# PCB_Draft_4.net
KiCad netlist of a schematic drawn in EAGLE
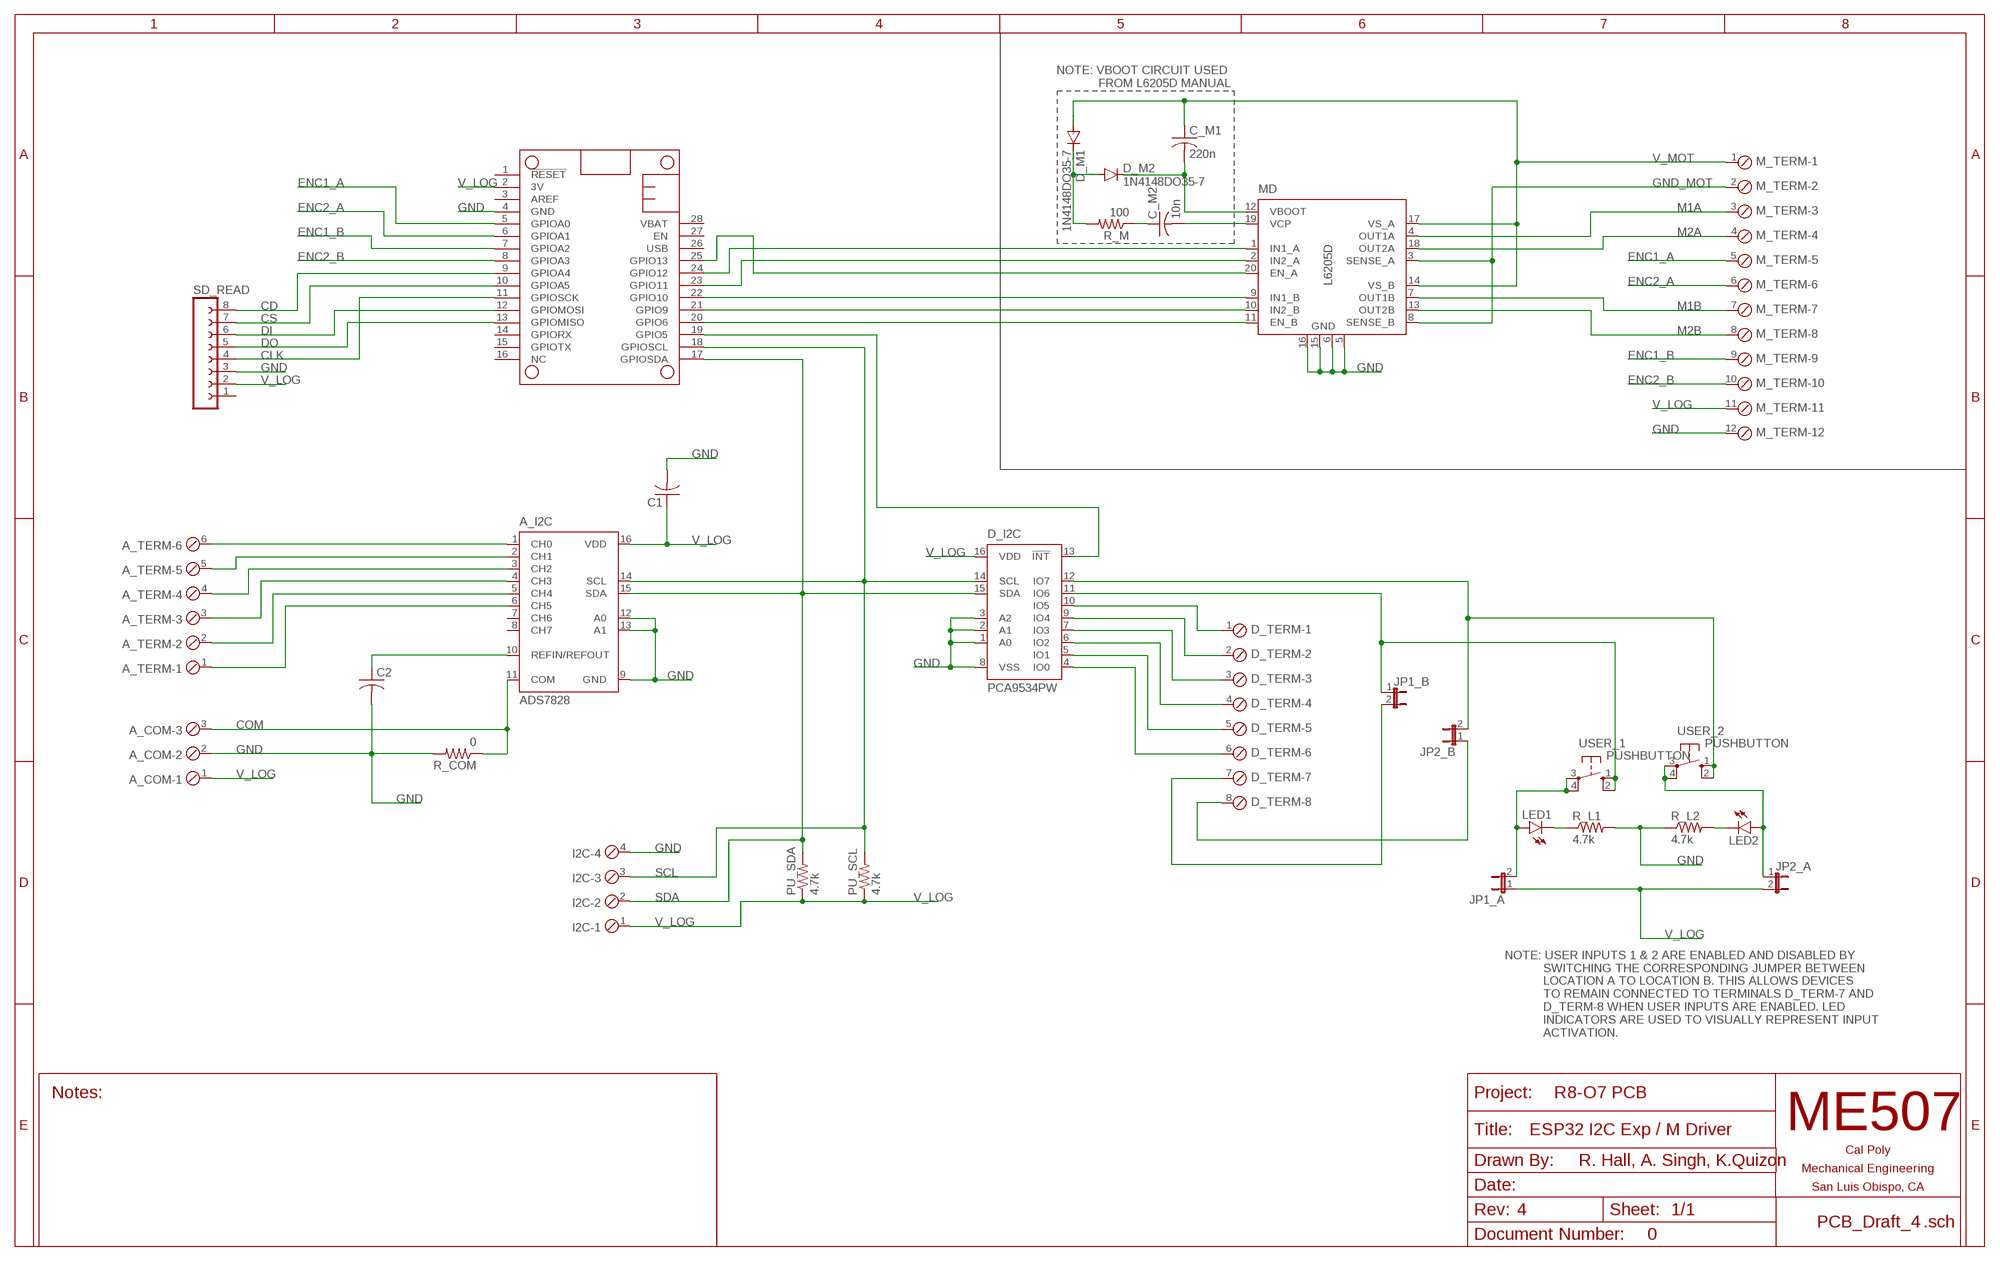
[diagram p0: schematic, sheet 1]

(export (version "E")
  (design (tool "Eeschema 10.0.6"))
  (components
    (comp (ref "A_COM")
      (value "SCREWTERM_3P_254")
      (footprint "eagle-import:3POL254")
      (libsource (lib "eagle-import") (part "SCREWTERM_3P_254"))
    )
    (comp (ref "A_I2C")
      (value "ADS7828")
      (footprint "eagle-import:TSSOP16-PW")
      (fields (field (name "MF") "TEXAS INSTRUMENTS") (field (name "MPN") "ADS7828E/250"))
      (libsource (lib "eagle-import") (part "ADS7828"))
    )
    (comp (ref "A_TERM")
      (value "SCREWTERM_6P_254")
      (footprint "eagle-import:6POL254")
      (libsource (lib "eagle-import") (part "SCREWTERM_6P_254"))
    )
    (comp (ref "C1")
      (value "C-USC0805")
      (footprint "eagle-import:C0805")
      (libsource (lib "eagle-import") (part "C-USC0805"))
    )
    (comp (ref "C2")
      (value "C-USC0805")
      (footprint "eagle-import:C0805")
      (libsource (lib "eagle-import") (part "C-USC0805"))
    )
    (comp (ref "C_M1")
      (value "220n")
      (footprint "eagle-import:C0805")
      (libsource (lib "eagle-import") (part "C-USC0805"))
    )
    (comp (ref "C_M2")
      (value "10n")
      (footprint "eagle-import:C0805")
      (libsource (lib "eagle-import") (part "C-USC0805"))
    )
    (comp (ref "D_I2C")
      (value "PCA9534PW")
      (footprint "eagle-import:TSSOP16")
      (libsource (lib "eagle-import") (part "PCA9534PW"))
    )
    (comp (ref "D_M1")
      (value "1N4148DO35-7")
      (footprint "eagle-import:DO35-7")
      (libsource (lib "eagle-import") (part "1N4148DO35-7"))
    )
    (comp (ref "D_M2")
      (value "1N4148DO35-7")
      (footprint "eagle-import:DO35-7")
      (libsource (lib "eagle-import") (part "1N4148DO35-7"))
    )
    (comp (ref "D_TERM")
      (value "SCREWTERM_8P_254")
      (footprint "eagle-import:8POL254")
      (libsource (lib "eagle-import") (part "SCREWTERM_8P_254"))
    )
    (comp (ref "FTHRWNG")
      (value "FEATHERWINGEXTENDED_BOTH_ENDS")
      (footprint "eagle-import:FEATHERWING")
      (libsource (lib "eagle-import") (part "FEATHERWINGEXTENDED_BOTH_ENDS"))
    )
    (comp (ref "I2C")
      (value "SCREWTERM_4P_254")
      (footprint "eagle-import:4POL254")
      (libsource (lib "eagle-import") (part "SCREWTERM_4P_254"))
    )
    (comp (ref "JP1_A")
      (value "JP1E")
      (footprint "eagle-import:JP1")
      (libsource (lib "eagle-import") (part "JP1E"))
    )
    (comp (ref "JP1_B")
      (value "JP1E")
      (footprint "eagle-import:JP1")
      (libsource (lib "eagle-import") (part "JP1E"))
    )
    (comp (ref "JP2_A")
      (value "JP1E")
      (footprint "eagle-import:JP1")
      (libsource (lib "eagle-import") (part "JP1E"))
    )
    (comp (ref "JP2_B")
      (value "JP1E")
      (footprint "eagle-import:JP1")
      (libsource (lib "eagle-import") (part "JP1E"))
    )
    (comp (ref "LED1")
      (value "LEDCHIP-LED0805")
      (footprint "eagle-import:CHIP-LED0805")
      (libsource (lib "eagle-import") (part "LEDCHIP-LED0805"))
    )
    (comp (ref "LED2")
      (value "LEDCHIP-LED0805")
      (footprint "eagle-import:CHIP-LED0805")
      (libsource (lib "eagle-import") (part "LEDCHIP-LED0805"))
    )
    (comp (ref "MD")
      (value "L6205D")
      (footprint "eagle-import:SO20")
      (libsource (lib "eagle-import") (part "L6205D"))
    )
    (comp (ref "M_TERM")
      (value "SCREWTERM_12P_254")
      (footprint "eagle-import:12POL254")
      (libsource (lib "eagle-import") (part "SCREWTERM_12P_254"))
    )
    (comp (ref "PU_SCL")
      (value "4.7k")
      (footprint "eagle-import:M0805")
      (libsource (lib "eagle-import") (part "R-US_M0805"))
    )
    (comp (ref "PU_SDA")
      (value "4.7k")
      (footprint "eagle-import:M0805")
      (libsource (lib "eagle-import") (part "R-US_M0805"))
    )
    (comp (ref "R_COM")
      (value "0")
      (footprint "eagle-import:M0805")
      (libsource (lib "eagle-import") (part "R-US_M0805"))
    )
    (comp (ref "R_L1")
      (value "4.7k")
      (footprint "eagle-import:M0805")
      (libsource (lib "eagle-import") (part "R-US_M0805"))
    )
    (comp (ref "R_L2")
      (value "4.7k")
      (footprint "eagle-import:M0805")
      (libsource (lib "eagle-import") (part "R-US_M0805"))
    )
    (comp (ref "R_M")
      (value "100")
      (footprint "eagle-import:M0805")
      (libsource (lib "eagle-import") (part "R-US_M0805"))
    )
    (comp (ref "SD_READ")
      (value "FE08-1")
      (footprint "eagle-import:FE08")
      (libsource (lib "eagle-import") (part "FE08-1"))
    )
    (comp (ref "USER_1")
      (value "PUSHBUTTON")
      (footprint "eagle-import:B3F-10XX")
      (fields (field (name "MPN") "B3F-1000"))
      (libsource (lib "eagle-import") (part "PUSHBUTTON"))
    )
    (comp (ref "USER_2")
      (value "PUSHBUTTON")
      (footprint "eagle-import:B3F-10XX")
      (fields (field (name "MPN") "B3F-1000"))
      (libsource (lib "eagle-import") (part "PUSHBUTTON"))
    )
  )
  (nets
    (net (code "1") (name "/CD") (class "Default")
      (node (ref "FTHRWNG") (pin "9") (pinfunction "GPIOA4_9") (pintype "bidirectional"))
      (node (ref "SD_READ") (pin "8") (pinfunction "8_8") (pintype "passive"))
    )
    (net (code "2") (name "/CLK") (class "Default")
      (node (ref "FTHRWNG") (pin "11") (pinfunction "GPIOSCK_11") (pintype "bidirectional"))
      (node (ref "SD_READ") (pin "4") (pinfunction "4_4") (pintype "passive"))
    )
    (net (code "3") (name "/COM") (class "Default")
      (node (ref "A_COM") (pin "3") (pinfunction "1_3") (pintype "passive"))
      (node (ref "A_I2C") (pin "11") (pinfunction "COM_11") (pintype "input"))
      (node (ref "R_COM") (pin "1") (pinfunction "1_1") (pintype "passive"))
    )
    (net (code "4") (name "/CS") (class "Default")
      (node (ref "FTHRWNG") (pin "10") (pinfunction "GPIOA5_10") (pintype "bidirectional"))
      (node (ref "SD_READ") (pin "7") (pinfunction "7_7") (pintype "passive"))
    )
    (net (code "5") (name "/DI") (class "Default")
      (node (ref "FTHRWNG") (pin "12") (pinfunction "GPIOMOSI_12") (pintype "bidirectional"))
      (node (ref "SD_READ") (pin "6") (pinfunction "6_6") (pintype "passive"))
    )
    (net (code "6") (name "/DO") (class "Default")
      (node (ref "FTHRWNG") (pin "13") (pinfunction "GPIOMISO_13") (pintype "bidirectional"))
      (node (ref "SD_READ") (pin "5") (pinfunction "5_5") (pintype "passive"))
    )
    (net (code "7") (name "/ENC1_A") (class "Default")
      (node (ref "FTHRWNG") (pin "5") (pinfunction "GPIOA0_5") (pintype "bidirectional"))
      (node (ref "M_TERM") (pin "5") (pinfunction "1_5") (pintype "passive"))
    )
    (net (code "8") (name "/ENC1_B") (class "Default")
      (node (ref "FTHRWNG") (pin "7") (pinfunction "GPIOA2_7") (pintype "bidirectional"))
      (node (ref "M_TERM") (pin "9") (pinfunction "1_9") (pintype "passive"))
    )
    (net (code "9") (name "/ENC2_A") (class "Default")
      (node (ref "FTHRWNG") (pin "6") (pinfunction "GPIOA1_6") (pintype "bidirectional"))
      (node (ref "M_TERM") (pin "6") (pinfunction "1_6") (pintype "passive"))
    )
    (net (code "10") (name "/ENC2_B") (class "Default")
      (node (ref "FTHRWNG") (pin "8") (pinfunction "GPIOA3_8") (pintype "bidirectional"))
      (node (ref "M_TERM") (pin "10") (pinfunction "1_10") (pintype "passive"))
    )
    (net (code "11") (name "/GND") (class "Default")
      (node (ref "A_COM") (pin "2") (pinfunction "1_2") (pintype "passive"))
      (node (ref "A_I2C") (pin "12") (pinfunction "A0_12") (pintype "input"))
      (node (ref "A_I2C") (pin "13") (pinfunction "A1_13") (pintype "input"))
      (node (ref "A_I2C") (pin "9") (pinfunction "GND_9") (pintype "power_in"))
      (node (ref "C1") (pin "2") (pinfunction "2_2") (pintype "passive"))
      (node (ref "C2") (pin "2") (pinfunction "2_2") (pintype "passive"))
      (node (ref "D_I2C") (pin "1") (pinfunction "A0_1") (pintype "input"))
      (node (ref "D_I2C") (pin "2") (pinfunction "A1_2") (pintype "input"))
      (node (ref "D_I2C") (pin "3") (pinfunction "A2_3") (pintype "input"))
      (node (ref "D_I2C") (pin "8") (pinfunction "VSS_8") (pintype "power_in"))
      (node (ref "FTHRWNG") (pin "4") (pinfunction "GND_4") (pintype "power_in"))
      (node (ref "I2C") (pin "4") (pinfunction "1_4") (pintype "passive"))
      (node (ref "MD") (pin "15") (pinfunction "GND_15") (pintype "power_in"))
      (node (ref "MD") (pin "16") (pinfunction "GND_16") (pintype "power_in"))
      (node (ref "MD") (pin "5") (pinfunction "GND_5") (pintype "power_in"))
      (node (ref "MD") (pin "6") (pinfunction "GND_6") (pintype "power_in"))
      (node (ref "M_TERM") (pin "12") (pinfunction "1_12") (pintype "passive"))
      (node (ref "R_COM") (pin "2") (pinfunction "2_2") (pintype "passive"))
      (node (ref "R_L1") (pin "2") (pinfunction "2_2") (pintype "passive"))
      (node (ref "R_L2") (pin "1") (pinfunction "1_1") (pintype "passive"))
      (node (ref "SD_READ") (pin "3") (pinfunction "3_3") (pintype "passive"))
    )
    (net (code "12") (name "/GND_MOT") (class "Default")
      (node (ref "MD") (pin "3") (pinfunction "SENSE_A_3") (pintype "input"))
      (node (ref "MD") (pin "8") (pinfunction "SENSE_B_8") (pintype "input"))
      (node (ref "M_TERM") (pin "2") (pinfunction "1_2") (pintype "passive"))
    )
    (net (code "13") (name "/M1A") (class "Default")
      (node (ref "MD") (pin "4") (pinfunction "OUT1A_4") (pintype "output"))
      (node (ref "M_TERM") (pin "3") (pinfunction "1_3") (pintype "passive"))
    )
    (net (code "14") (name "/M1B") (class "Default")
      (node (ref "MD") (pin "7") (pinfunction "OUT1B_7") (pintype "output"))
      (node (ref "M_TERM") (pin "7") (pinfunction "1_7") (pintype "passive"))
    )
    (net (code "15") (name "/M2A") (class "Default")
      (node (ref "MD") (pin "18") (pinfunction "OUT2A_18") (pintype "output"))
      (node (ref "M_TERM") (pin "4") (pinfunction "1_4") (pintype "passive"))
    )
    (net (code "16") (name "/M2B") (class "Default")
      (node (ref "MD") (pin "13") (pinfunction "OUT2B_13") (pintype "output"))
      (node (ref "M_TERM") (pin "8") (pinfunction "1_8") (pintype "passive"))
    )
    (net (code "17") (name "/SCL") (class "Default")
      (node (ref "A_I2C") (pin "14") (pinfunction "SCL_14") (pintype "input"))
      (node (ref "D_I2C") (pin "14") (pinfunction "SCL_14") (pintype "input"))
      (node (ref "FTHRWNG") (pin "18") (pinfunction "GPIOSCL_18") (pintype "bidirectional"))
      (node (ref "I2C") (pin "3") (pinfunction "1_3") (pintype "passive"))
      (node (ref "PU_SCL") (pin "2") (pinfunction "2_2") (pintype "passive"))
    )
    (net (code "18") (name "/SDA") (class "Default")
      (node (ref "A_I2C") (pin "15") (pinfunction "SDA_15") (pintype "bidirectional"))
      (node (ref "D_I2C") (pin "15") (pinfunction "SDA_15") (pintype "bidirectional"))
      (node (ref "FTHRWNG") (pin "17") (pinfunction "GPIOSDA_17") (pintype "bidirectional"))
      (node (ref "I2C") (pin "2") (pinfunction "1_2") (pintype "passive"))
      (node (ref "PU_SDA") (pin "2") (pinfunction "2_2") (pintype "passive"))
    )
    (net (code "19") (name "/USB") (class "Default")
      (node (ref "FTHRWNG") (pin "26") (pinfunction "USB_26") (pintype "power_in"))
    )
    (net (code "20") (name "/VBAT") (class "Default")
      (node (ref "FTHRWNG") (pin "28") (pinfunction "VBAT_28") (pintype "power_in"))
    )
    (net (code "21") (name "/V_LOG") (class "Default")
      (node (ref "A_COM") (pin "1") (pinfunction "1_1") (pintype "passive"))
      (node (ref "A_I2C") (pin "16") (pinfunction "VDD_16") (pintype "power_in"))
      (node (ref "C1") (pin "1") (pinfunction "1_1") (pintype "passive"))
      (node (ref "D_I2C") (pin "16") (pinfunction "VDD_16") (pintype "power_in"))
      (node (ref "FTHRWNG") (pin "2") (pinfunction "3V_2") (pintype "power_in"))
      (node (ref "I2C") (pin "1") (pinfunction "1_1") (pintype "passive"))
      (node (ref "JP1_A") (pin "1") (pinfunction "1_1") (pintype "passive"))
      (node (ref "JP2_A") (pin "2") (pinfunction "2_2") (pintype "passive"))
      (node (ref "M_TERM") (pin "11") (pinfunction "1_11") (pintype "passive"))
      (node (ref "PU_SCL") (pin "1") (pinfunction "1_1") (pintype "passive"))
      (node (ref "PU_SDA") (pin "1") (pinfunction "1_1") (pintype "passive"))
      (node (ref "SD_READ") (pin "2") (pinfunction "2_2") (pintype "passive"))
    )
    (net (code "22") (name "/V_MOT") (class "Default")
      (node (ref "C_M1") (pin "1") (pinfunction "1_1") (pintype "passive"))
      (node (ref "D_M1") (pin "A") (pinfunction "A_A") (pintype "passive"))
      (node (ref "MD") (pin "14") (pinfunction "VS_B_14") (pintype "power_in"))
      (node (ref "MD") (pin "17") (pinfunction "VS_A_17") (pintype "power_in"))
      (node (ref "M_TERM") (pin "1") (pinfunction "1_1") (pintype "passive"))
    )
    (net (code "23") (name "Net-(A_I2C-CH0)") (class "Default")
      (node (ref "A_I2C") (pin "1") (pinfunction "CH0_1") (pintype "input"))
      (node (ref "A_TERM") (pin "6") (pinfunction "1_6") (pintype "passive"))
    )
    (net (code "24") (name "Net-(A_I2C-CH1)") (class "Default")
      (node (ref "A_I2C") (pin "2") (pinfunction "CH1_2") (pintype "input"))
      (node (ref "A_TERM") (pin "5") (pinfunction "1_5") (pintype "passive"))
    )
    (net (code "25") (name "Net-(A_I2C-CH2)") (class "Default")
      (node (ref "A_I2C") (pin "3") (pinfunction "CH2_3") (pintype "input"))
      (node (ref "A_TERM") (pin "4") (pinfunction "1_4") (pintype "passive"))
    )
    (net (code "26") (name "Net-(A_I2C-CH3)") (class "Default")
      (node (ref "A_I2C") (pin "4") (pinfunction "CH3_4") (pintype "input"))
      (node (ref "A_TERM") (pin "3") (pinfunction "1_3") (pintype "passive"))
    )
    (net (code "27") (name "Net-(A_I2C-CH4)") (class "Default")
      (node (ref "A_I2C") (pin "5") (pinfunction "CH4_5") (pintype "input"))
      (node (ref "A_TERM") (pin "2") (pinfunction "1_2") (pintype "passive"))
    )
    (net (code "28") (name "Net-(A_I2C-CH5)") (class "Default")
      (node (ref "A_I2C") (pin "6") (pinfunction "CH5_6") (pintype "input"))
      (node (ref "A_TERM") (pin "1") (pinfunction "1_1") (pintype "passive"))
    )
    (net (code "29") (name "Net-(A_I2C-REFIN{slash}REFOUT)") (class "Default")
      (node (ref "A_I2C") (pin "10") (pinfunction "REFIN/REFOUT_10") (pintype "passive"))
      (node (ref "C2") (pin "1") (pinfunction "1_1") (pintype "passive"))
    )
    (net (code "30") (name "Net-(C_M2-Pad1)") (class "Default")
      (node (ref "C_M2") (pin "1") (pinfunction "1_1") (pintype "passive"))
      (node (ref "R_M") (pin "1") (pinfunction "1_1") (pintype "passive"))
    )
    (net (code "31") (name "Net-(D_I2C-IO0)") (class "Default")
      (node (ref "D_I2C") (pin "4") (pinfunction "IO0_4") (pintype "bidirectional"))
      (node (ref "D_TERM") (pin "6") (pinfunction "1_6") (pintype "passive"))
    )
    (net (code "32") (name "Net-(D_I2C-IO1)") (class "Default")
      (node (ref "D_I2C") (pin "5") (pinfunction "IO1_5") (pintype "bidirectional"))
      (node (ref "D_TERM") (pin "5") (pinfunction "1_5") (pintype "passive"))
    )
    (net (code "33") (name "Net-(D_I2C-IO2)") (class "Default")
      (node (ref "D_I2C") (pin "6") (pinfunction "IO2_6") (pintype "bidirectional"))
      (node (ref "D_TERM") (pin "4") (pinfunction "1_4") (pintype "passive"))
    )
    (net (code "34") (name "Net-(D_I2C-IO3)") (class "Default")
      (node (ref "D_I2C") (pin "7") (pinfunction "IO3_7") (pintype "bidirectional"))
      (node (ref "D_TERM") (pin "3") (pinfunction "1_3") (pintype "passive"))
    )
    (net (code "35") (name "Net-(D_I2C-IO4)") (class "Default")
      (node (ref "D_I2C") (pin "9") (pinfunction "IO4_9") (pintype "bidirectional"))
      (node (ref "D_TERM") (pin "2") (pinfunction "1_2") (pintype "passive"))
    )
    (net (code "36") (name "Net-(D_I2C-IO5)") (class "Default")
      (node (ref "D_I2C") (pin "10") (pinfunction "IO5_10") (pintype "bidirectional"))
      (node (ref "D_TERM") (pin "1") (pinfunction "1_1") (pintype "passive"))
    )
    (net (code "37") (name "Net-(D_I2C-IO6)") (class "Default")
      (node (ref "D_I2C") (pin "11") (pinfunction "IO6_11") (pintype "bidirectional"))
      (node (ref "JP1_B") (pin "1") (pinfunction "1_1") (pintype "passive"))
      (node (ref "USER_1") (pin "1") (pinfunction "S_1") (pintype "passive"))
      (node (ref "USER_1") (pin "2") (pinfunction "S1_2") (pintype "passive"))
    )
    (net (code "38") (name "Net-(D_I2C-IO7)") (class "Default")
      (node (ref "D_I2C") (pin "12") (pinfunction "IO7_12") (pintype "bidirectional"))
      (node (ref "JP2_B") (pin "2") (pinfunction "2_2") (pintype "passive"))
      (node (ref "USER_2") (pin "1") (pinfunction "S_1") (pintype "passive"))
      (node (ref "USER_2") (pin "2") (pinfunction "S1_2") (pintype "passive"))
    )
    (net (code "39") (name "Net-(D_I2C-~{INT})") (class "Default")
      (node (ref "D_I2C") (pin "13") (pinfunction "~{INT}_13") (pintype "open_collector"))
      (node (ref "FTHRWNG") (pin "19") (pinfunction "GPIO5_19") (pintype "bidirectional"))
    )
    (net (code "40") (name "Net-(D_M1-PadC)") (class "Default")
      (node (ref "D_M1") (pin "C") (pinfunction "C_C") (pintype "passive"))
      (node (ref "D_M2") (pin "A") (pinfunction "A_A") (pintype "passive"))
      (node (ref "R_M") (pin "2") (pinfunction "2_2") (pintype "passive"))
    )
    (net (code "41") (name "Net-(D_TERMG-1)") (class "Default")
      (node (ref "D_TERM") (pin "7") (pinfunction "1_7") (pintype "passive"))
      (node (ref "JP1_B") (pin "2") (pinfunction "2_2") (pintype "passive"))
    )
    (net (code "42") (name "Net-(D_TERMH-1)") (class "Default")
      (node (ref "D_TERM") (pin "8") (pinfunction "1_8") (pintype "passive"))
      (node (ref "JP2_B") (pin "1") (pinfunction "1_1") (pintype "passive"))
    )
    (net (code "43") (name "Net-(FTHRWNG-GPIO6)") (class "Default")
      (node (ref "FTHRWNG") (pin "20") (pinfunction "GPIO6_20") (pintype "bidirectional"))
      (node (ref "MD") (pin "11") (pinfunction "EN_B_11") (pintype "input"))
    )
    (net (code "44") (name "Net-(FTHRWNG-GPIO9)") (class "Default")
      (node (ref "FTHRWNG") (pin "21") (pinfunction "GPIO9_21") (pintype "bidirectional"))
      (node (ref "MD") (pin "10") (pinfunction "IN2_B_10") (pintype "input"))
    )
    (net (code "45") (name "Net-(FTHRWNG-GPIO10)") (class "Default")
      (node (ref "FTHRWNG") (pin "22") (pinfunction "GPIO10_22") (pintype "bidirectional"))
      (node (ref "MD") (pin "9") (pinfunction "IN1_B_9") (pintype "input"))
    )
    (net (code "46") (name "Net-(FTHRWNG-GPIO11)") (class "Default")
      (node (ref "FTHRWNG") (pin "23") (pinfunction "GPIO11_23") (pintype "bidirectional"))
      (node (ref "MD") (pin "2") (pinfunction "IN2_A_2") (pintype "input"))
    )
    (net (code "47") (name "Net-(FTHRWNG-GPIO12)") (class "Default")
      (node (ref "FTHRWNG") (pin "24") (pinfunction "GPIO12_24") (pintype "bidirectional"))
      (node (ref "MD") (pin "1") (pinfunction "IN1_A_1") (pintype "input"))
    )
    (net (code "48") (name "Net-(FTHRWNG-GPIO13)") (class "Default")
      (node (ref "FTHRWNG") (pin "25") (pinfunction "GPIO13_25") (pintype "bidirectional"))
      (node (ref "MD") (pin "20") (pinfunction "EN_A_20") (pintype "input"))
    )
    (net (code "49") (name "Net-(LED1-PadC)") (class "Default")
      (node (ref "LED1") (pin "C") (pinfunction "C_C") (pintype "passive"))
      (node (ref "R_L1") (pin "1") (pinfunction "1_1") (pintype "passive"))
    )
    (net (code "50") (name "Net-(LED2-PadC)") (class "Default")
      (node (ref "LED2") (pin "C") (pinfunction "C_C") (pintype "passive"))
      (node (ref "R_L2") (pin "2") (pinfunction "2_2") (pintype "passive"))
    )
    (net (code "51") (name "Net-(MD-VBOOT)") (class "Default")
      (node (ref "C_M1") (pin "2") (pinfunction "2_2") (pintype "passive"))
      (node (ref "D_M2") (pin "C") (pinfunction "C_C") (pintype "passive"))
      (node (ref "MD") (pin "12") (pinfunction "VBOOT_12") (pintype "power_in"))
    )
    (net (code "52") (name "Net-(MD-VCP)") (class "Default")
      (node (ref "C_M2") (pin "2") (pinfunction "2_2") (pintype "passive"))
      (node (ref "MD") (pin "19") (pinfunction "VCP_19") (pintype "power_in"))
    )
    (net (code "53") (name "Net-(USER_1-P)") (class "Default")
      (node (ref "JP1_A") (pin "2") (pinfunction "2_2") (pintype "passive"))
      (node (ref "LED1") (pin "A") (pinfunction "A_A") (pintype "passive"))
      (node (ref "USER_1") (pin "3") (pinfunction "P_3") (pintype "passive"))
      (node (ref "USER_1") (pin "4") (pinfunction "P1_4") (pintype "passive"))
    )
    (net (code "54") (name "Net-(USER_2-P)") (class "Default")
      (node (ref "JP2_A") (pin "1") (pinfunction "1_1") (pintype "passive"))
      (node (ref "LED2") (pin "A") (pinfunction "A_A") (pintype "passive"))
      (node (ref "USER_2") (pin "3") (pinfunction "P_3") (pintype "passive"))
      (node (ref "USER_2") (pin "4") (pinfunction "P1_4") (pintype "passive"))
    )
    (net (code "55") (name "unconnected-(A_I2C-CH6-Pad7)") (class "Default")
      (node (ref "A_I2C") (pin "7") (pinfunction "CH6_7") (pintype "input"))
    )
    (net (code "56") (name "unconnected-(A_I2C-CH7-Pad8)") (class "Default")
      (node (ref "A_I2C") (pin "8") (pinfunction "CH7_8") (pintype "input"))
    )
    (net (code "57") (name "unconnected-(FTHRWNG-AREF-Pad3)") (class "Default")
      (node (ref "FTHRWNG") (pin "3") (pinfunction "AREF_3") (pintype "passive"))
    )
    (net (code "58") (name "unconnected-(FTHRWNG-EN-Pad27)") (class "Default")
      (node (ref "FTHRWNG") (pin "27") (pinfunction "EN_27") (pintype "passive"))
    )
    (net (code "59") (name "unconnected-(FTHRWNG-GPIORX-Pad14)") (class "Default")
      (node (ref "FTHRWNG") (pin "14") (pinfunction "GPIORX_14") (pintype "bidirectional"))
    )
    (net (code "60") (name "unconnected-(FTHRWNG-GPIOTX-Pad15)") (class "Default")
      (node (ref "FTHRWNG") (pin "15") (pinfunction "GPIOTX_15") (pintype "bidirectional"))
    )
    (net (code "61") (name "unconnected-(FTHRWNG-NC-Pad16)") (class "Default")
      (node (ref "FTHRWNG") (pin "16") (pinfunction "NC_16") (pintype "passive"))
    )
    (net (code "62") (name "unconnected-(FTHRWNG-~{RESET}-Pad1)") (class "Default")
      (node (ref "FTHRWNG") (pin "1") (pinfunction "~{RESET}_1") (pintype "input"))
    )
    (net (code "63") (name "unconnected-(SD_READ-Pad1)") (class "Default")
      (node (ref "SD_READ") (pin "1") (pinfunction "1_1") (pintype "passive"))
    )
  )
)
